# 48-pin.net
KiCad netlist of a schematic drawn in EAGLE
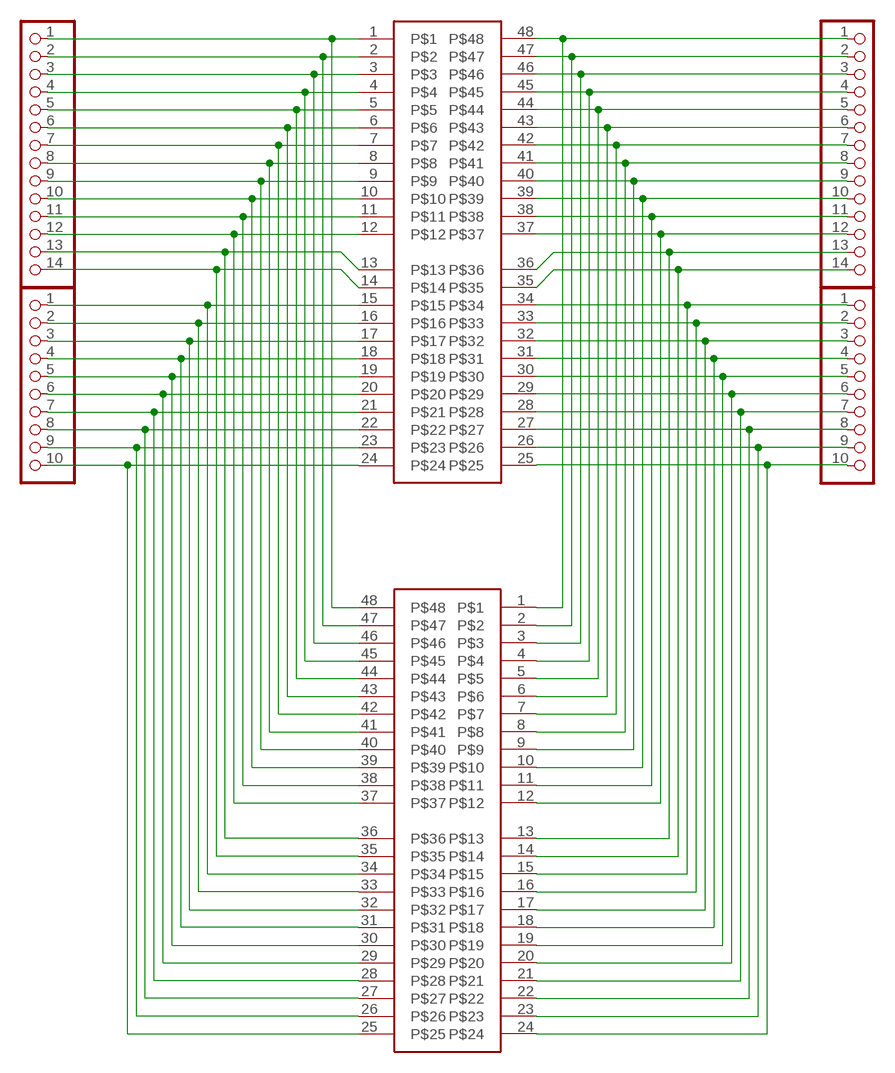
[diagram p0: schematic, sheet 1]

(export (version "E")
  (design (tool "Eeschema 10.0.6"))
  (components
    (comp (ref "JP1")
      (value "PADS-14")
      (footprint "eagle-import:PADS-14")
      (libsource (lib "eagle-import") (part "PADS-14"))
    )
    (comp (ref "JP2")
      (value "PADS-14")
      (footprint "eagle-import:PADS-14")
      (libsource (lib "eagle-import") (part "PADS-14"))
    )
    (comp (ref "JP3")
      (value "PADS-10")
      (footprint "eagle-import:PADS-10")
      (libsource (lib "eagle-import") (part "PADS-10"))
    )
    (comp (ref "JP4")
      (value "PADS-10")
      (footprint "eagle-import:PADS-10")
      (libsource (lib "eagle-import") (part "PADS-10"))
    )
    (comp (ref "U$1")
      (value "BREAKOUTS_48-PINTQFP")
      (footprint "eagle-import:BREAKOUTS_TQFP48")
      (libsource (lib "eagle-import") (part "BREAKOUTS_48-PINTQFP"))
    )
    (comp (ref "U$2")
      (value "BREAKOUTS_48-PINQFN")
      (footprint "eagle-import:BREAKOUTS_QFN48")
      (libsource (lib "eagle-import") (part "BREAKOUTS_48-PINQFN"))
    )
  )
  (nets
    (net (code "1") (name "Net-(U$1-P$1)") (class "Default")
      (node (ref "JP1") (pin "1") (pinfunction "1_1") (pintype "passive"))
      (node (ref "U$1") (pin "1") (pinfunction "P$1_1") (pintype "bidirectional"))
      (node (ref "U$2") (pin "48") (pinfunction "P$48_48") (pintype "bidirectional"))
    )
    (net (code "2") (name "Net-(U$1-P$2)") (class "Default")
      (node (ref "JP1") (pin "2") (pinfunction "2_2") (pintype "passive"))
      (node (ref "U$1") (pin "2") (pinfunction "P$2_2") (pintype "bidirectional"))
      (node (ref "U$2") (pin "47") (pinfunction "P$47_47") (pintype "bidirectional"))
    )
    (net (code "3") (name "Net-(U$1-P$3)") (class "Default")
      (node (ref "JP1") (pin "3") (pinfunction "3_3") (pintype "passive"))
      (node (ref "U$1") (pin "3") (pinfunction "P$3_3") (pintype "bidirectional"))
      (node (ref "U$2") (pin "46") (pinfunction "P$46_46") (pintype "bidirectional"))
    )
    (net (code "4") (name "Net-(U$1-P$4)") (class "Default")
      (node (ref "JP1") (pin "4") (pinfunction "4_4") (pintype "passive"))
      (node (ref "U$1") (pin "4") (pinfunction "P$4_4") (pintype "bidirectional"))
      (node (ref "U$2") (pin "45") (pinfunction "P$45_45") (pintype "bidirectional"))
    )
    (net (code "5") (name "Net-(U$1-P$5)") (class "Default")
      (node (ref "JP1") (pin "5") (pinfunction "5_5") (pintype "passive"))
      (node (ref "U$1") (pin "5") (pinfunction "P$5_5") (pintype "bidirectional"))
      (node (ref "U$2") (pin "44") (pinfunction "P$44_44") (pintype "bidirectional"))
    )
    (net (code "6") (name "Net-(U$1-P$6)") (class "Default")
      (node (ref "JP1") (pin "6") (pinfunction "6_6") (pintype "passive"))
      (node (ref "U$1") (pin "6") (pinfunction "P$6_6") (pintype "bidirectional"))
      (node (ref "U$2") (pin "43") (pinfunction "P$43_43") (pintype "bidirectional"))
    )
    (net (code "7") (name "Net-(U$1-P$7)") (class "Default")
      (node (ref "JP1") (pin "7") (pinfunction "7_7") (pintype "passive"))
      (node (ref "U$1") (pin "7") (pinfunction "P$7_7") (pintype "bidirectional"))
      (node (ref "U$2") (pin "42") (pinfunction "P$42_42") (pintype "bidirectional"))
    )
    (net (code "8") (name "Net-(U$1-P$8)") (class "Default")
      (node (ref "JP1") (pin "8") (pinfunction "8_8") (pintype "passive"))
      (node (ref "U$1") (pin "8") (pinfunction "P$8_8") (pintype "bidirectional"))
      (node (ref "U$2") (pin "41") (pinfunction "P$41_41") (pintype "bidirectional"))
    )
    (net (code "9") (name "Net-(U$1-P$9)") (class "Default")
      (node (ref "JP1") (pin "9") (pinfunction "9_9") (pintype "passive"))
      (node (ref "U$1") (pin "9") (pinfunction "P$9_9") (pintype "bidirectional"))
      (node (ref "U$2") (pin "40") (pinfunction "P$40_40") (pintype "bidirectional"))
    )
    (net (code "10") (name "Net-(U$1-P$10)") (class "Default")
      (node (ref "JP1") (pin "10") (pinfunction "10_10") (pintype "passive"))
      (node (ref "U$1") (pin "10") (pinfunction "P$10_10") (pintype "bidirectional"))
      (node (ref "U$2") (pin "39") (pinfunction "P$39_39") (pintype "bidirectional"))
    )
    (net (code "11") (name "Net-(U$1-P$11)") (class "Default")
      (node (ref "JP1") (pin "11") (pinfunction "11_11") (pintype "passive"))
      (node (ref "U$1") (pin "11") (pinfunction "P$11_11") (pintype "bidirectional"))
      (node (ref "U$2") (pin "38") (pinfunction "P$38_38") (pintype "bidirectional"))
    )
    (net (code "12") (name "Net-(U$1-P$12)") (class "Default")
      (node (ref "JP1") (pin "12") (pinfunction "12_12") (pintype "passive"))
      (node (ref "U$1") (pin "12") (pinfunction "P$12_12") (pintype "bidirectional"))
      (node (ref "U$2") (pin "37") (pinfunction "P$37_37") (pintype "bidirectional"))
    )
    (net (code "13") (name "Net-(U$1-P$13)") (class "Default")
      (node (ref "JP1") (pin "13") (pinfunction "13_13") (pintype "passive"))
      (node (ref "U$1") (pin "13") (pinfunction "P$13_13") (pintype "bidirectional"))
      (node (ref "U$2") (pin "36") (pinfunction "P$36_36") (pintype "bidirectional"))
    )
    (net (code "14") (name "Net-(U$1-P$14)") (class "Default")
      (node (ref "JP1") (pin "14") (pinfunction "14_14") (pintype "passive"))
      (node (ref "U$1") (pin "14") (pinfunction "P$14_14") (pintype "bidirectional"))
      (node (ref "U$2") (pin "35") (pinfunction "P$35_35") (pintype "bidirectional"))
    )
    (net (code "15") (name "Net-(U$1-P$15)") (class "Default")
      (node (ref "JP3") (pin "1") (pinfunction "1_1") (pintype "passive"))
      (node (ref "U$1") (pin "15") (pinfunction "P$15_15") (pintype "bidirectional"))
      (node (ref "U$2") (pin "34") (pinfunction "P$34_34") (pintype "bidirectional"))
    )
    (net (code "16") (name "Net-(U$1-P$16)") (class "Default")
      (node (ref "JP3") (pin "2") (pinfunction "2_2") (pintype "passive"))
      (node (ref "U$1") (pin "16") (pinfunction "P$16_16") (pintype "bidirectional"))
      (node (ref "U$2") (pin "33") (pinfunction "P$33_33") (pintype "bidirectional"))
    )
    (net (code "17") (name "Net-(U$1-P$17)") (class "Default")
      (node (ref "JP3") (pin "3") (pinfunction "3_3") (pintype "passive"))
      (node (ref "U$1") (pin "17") (pinfunction "P$17_17") (pintype "bidirectional"))
      (node (ref "U$2") (pin "32") (pinfunction "P$32_32") (pintype "bidirectional"))
    )
    (net (code "18") (name "Net-(U$1-P$18)") (class "Default")
      (node (ref "JP3") (pin "4") (pinfunction "4_4") (pintype "passive"))
      (node (ref "U$1") (pin "18") (pinfunction "P$18_18") (pintype "bidirectional"))
      (node (ref "U$2") (pin "31") (pinfunction "P$31_31") (pintype "bidirectional"))
    )
    (net (code "19") (name "Net-(U$1-P$19)") (class "Default")
      (node (ref "JP3") (pin "5") (pinfunction "5_5") (pintype "passive"))
      (node (ref "U$1") (pin "19") (pinfunction "P$19_19") (pintype "bidirectional"))
      (node (ref "U$2") (pin "30") (pinfunction "P$30_30") (pintype "bidirectional"))
    )
    (net (code "20") (name "Net-(U$1-P$20)") (class "Default")
      (node (ref "JP3") (pin "6") (pinfunction "6_6") (pintype "passive"))
      (node (ref "U$1") (pin "20") (pinfunction "P$20_20") (pintype "bidirectional"))
      (node (ref "U$2") (pin "29") (pinfunction "P$29_29") (pintype "bidirectional"))
    )
    (net (code "21") (name "Net-(U$1-P$21)") (class "Default")
      (node (ref "JP3") (pin "7") (pinfunction "7_7") (pintype "passive"))
      (node (ref "U$1") (pin "21") (pinfunction "P$21_21") (pintype "bidirectional"))
      (node (ref "U$2") (pin "28") (pinfunction "P$28_28") (pintype "bidirectional"))
    )
    (net (code "22") (name "Net-(U$1-P$22)") (class "Default")
      (node (ref "JP3") (pin "8") (pinfunction "8_8") (pintype "passive"))
      (node (ref "U$1") (pin "22") (pinfunction "P$22_22") (pintype "bidirectional"))
      (node (ref "U$2") (pin "27") (pinfunction "P$27_27") (pintype "bidirectional"))
    )
    (net (code "23") (name "Net-(U$1-P$23)") (class "Default")
      (node (ref "JP3") (pin "9") (pinfunction "9_9") (pintype "passive"))
      (node (ref "U$1") (pin "23") (pinfunction "P$23_23") (pintype "bidirectional"))
      (node (ref "U$2") (pin "26") (pinfunction "P$26_26") (pintype "bidirectional"))
    )
    (net (code "24") (name "Net-(U$1-P$24)") (class "Default")
      (node (ref "JP3") (pin "10") (pinfunction "10_10") (pintype "passive"))
      (node (ref "U$1") (pin "24") (pinfunction "P$24_24") (pintype "bidirectional"))
      (node (ref "U$2") (pin "25") (pinfunction "P$25_25") (pintype "bidirectional"))
    )
    (net (code "25") (name "Net-(U$1-P$25)") (class "Default")
      (node (ref "JP4") (pin "10") (pinfunction "10_10") (pintype "passive"))
      (node (ref "U$1") (pin "25") (pinfunction "P$25_25") (pintype "bidirectional"))
      (node (ref "U$2") (pin "24") (pinfunction "P$24_24") (pintype "bidirectional"))
    )
    (net (code "26") (name "Net-(U$1-P$26)") (class "Default")
      (node (ref "JP4") (pin "9") (pinfunction "9_9") (pintype "passive"))
      (node (ref "U$1") (pin "26") (pinfunction "P$26_26") (pintype "bidirectional"))
      (node (ref "U$2") (pin "23") (pinfunction "P$23_23") (pintype "bidirectional"))
    )
    (net (code "27") (name "Net-(U$1-P$27)") (class "Default")
      (node (ref "JP4") (pin "8") (pinfunction "8_8") (pintype "passive"))
      (node (ref "U$1") (pin "27") (pinfunction "P$27_27") (pintype "bidirectional"))
      (node (ref "U$2") (pin "22") (pinfunction "P$22_22") (pintype "bidirectional"))
    )
    (net (code "28") (name "Net-(U$1-P$28)") (class "Default")
      (node (ref "JP4") (pin "7") (pinfunction "7_7") (pintype "passive"))
      (node (ref "U$1") (pin "28") (pinfunction "P$28_28") (pintype "bidirectional"))
      (node (ref "U$2") (pin "21") (pinfunction "P$21_21") (pintype "bidirectional"))
    )
    (net (code "29") (name "Net-(U$1-P$29)") (class "Default")
      (node (ref "JP4") (pin "6") (pinfunction "6_6") (pintype "passive"))
      (node (ref "U$1") (pin "29") (pinfunction "P$29_29") (pintype "bidirectional"))
      (node (ref "U$2") (pin "20") (pinfunction "P$20_20") (pintype "bidirectional"))
    )
    (net (code "30") (name "Net-(U$1-P$30)") (class "Default")
      (node (ref "JP4") (pin "5") (pinfunction "5_5") (pintype "passive"))
      (node (ref "U$1") (pin "30") (pinfunction "P$30_30") (pintype "bidirectional"))
      (node (ref "U$2") (pin "19") (pinfunction "P$19_19") (pintype "bidirectional"))
    )
    (net (code "31") (name "Net-(U$1-P$31)") (class "Default")
      (node (ref "JP4") (pin "4") (pinfunction "4_4") (pintype "passive"))
      (node (ref "U$1") (pin "31") (pinfunction "P$31_31") (pintype "bidirectional"))
      (node (ref "U$2") (pin "18") (pinfunction "P$18_18") (pintype "bidirectional"))
    )
    (net (code "32") (name "Net-(U$1-P$32)") (class "Default")
      (node (ref "JP4") (pin "3") (pinfunction "3_3") (pintype "passive"))
      (node (ref "U$1") (pin "32") (pinfunction "P$32_32") (pintype "bidirectional"))
      (node (ref "U$2") (pin "17") (pinfunction "P$17_17") (pintype "bidirectional"))
    )
    (net (code "33") (name "Net-(U$1-P$33)") (class "Default")
      (node (ref "JP4") (pin "2") (pinfunction "2_2") (pintype "passive"))
      (node (ref "U$1") (pin "33") (pinfunction "P$33_33") (pintype "bidirectional"))
      (node (ref "U$2") (pin "16") (pinfunction "P$16_16") (pintype "bidirectional"))
    )
    (net (code "34") (name "Net-(U$1-P$34)") (class "Default")
      (node (ref "JP4") (pin "1") (pinfunction "1_1") (pintype "passive"))
      (node (ref "U$1") (pin "34") (pinfunction "P$34_34") (pintype "bidirectional"))
      (node (ref "U$2") (pin "15") (pinfunction "P$15_15") (pintype "bidirectional"))
    )
    (net (code "35") (name "Net-(U$1-P$35)") (class "Default")
      (node (ref "JP2") (pin "14") (pinfunction "14_14") (pintype "passive"))
      (node (ref "U$1") (pin "35") (pinfunction "P$35_35") (pintype "bidirectional"))
      (node (ref "U$2") (pin "14") (pinfunction "P$14_14") (pintype "bidirectional"))
    )
    (net (code "36") (name "Net-(U$1-P$36)") (class "Default")
      (node (ref "JP2") (pin "13") (pinfunction "13_13") (pintype "passive"))
      (node (ref "U$1") (pin "36") (pinfunction "P$36_36") (pintype "bidirectional"))
      (node (ref "U$2") (pin "13") (pinfunction "P$13_13") (pintype "bidirectional"))
    )
    (net (code "37") (name "Net-(U$1-P$37)") (class "Default")
      (node (ref "JP2") (pin "12") (pinfunction "12_12") (pintype "passive"))
      (node (ref "U$1") (pin "37") (pinfunction "P$37_37") (pintype "bidirectional"))
      (node (ref "U$2") (pin "12") (pinfunction "P$12_12") (pintype "bidirectional"))
    )
    (net (code "38") (name "Net-(U$1-P$38)") (class "Default")
      (node (ref "JP2") (pin "11") (pinfunction "11_11") (pintype "passive"))
      (node (ref "U$1") (pin "38") (pinfunction "P$38_38") (pintype "bidirectional"))
      (node (ref "U$2") (pin "11") (pinfunction "P$11_11") (pintype "bidirectional"))
    )
    (net (code "39") (name "Net-(U$1-P$39)") (class "Default")
      (node (ref "JP2") (pin "10") (pinfunction "10_10") (pintype "passive"))
      (node (ref "U$1") (pin "39") (pinfunction "P$39_39") (pintype "bidirectional"))
      (node (ref "U$2") (pin "10") (pinfunction "P$10_10") (pintype "bidirectional"))
    )
    (net (code "40") (name "Net-(U$1-P$40)") (class "Default")
      (node (ref "JP2") (pin "9") (pinfunction "9_9") (pintype "passive"))
      (node (ref "U$1") (pin "40") (pinfunction "P$40_40") (pintype "bidirectional"))
      (node (ref "U$2") (pin "9") (pinfunction "P$9_9") (pintype "bidirectional"))
    )
    (net (code "41") (name "Net-(U$1-P$41)") (class "Default")
      (node (ref "JP2") (pin "8") (pinfunction "8_8") (pintype "passive"))
      (node (ref "U$1") (pin "41") (pinfunction "P$41_41") (pintype "bidirectional"))
      (node (ref "U$2") (pin "8") (pinfunction "P$8_8") (pintype "bidirectional"))
    )
    (net (code "42") (name "Net-(U$1-P$42)") (class "Default")
      (node (ref "JP2") (pin "7") (pinfunction "7_7") (pintype "passive"))
      (node (ref "U$1") (pin "42") (pinfunction "P$42_42") (pintype "bidirectional"))
      (node (ref "U$2") (pin "7") (pinfunction "P$7_7") (pintype "bidirectional"))
    )
    (net (code "43") (name "Net-(U$1-P$43)") (class "Default")
      (node (ref "JP2") (pin "6") (pinfunction "6_6") (pintype "passive"))
      (node (ref "U$1") (pin "43") (pinfunction "P$43_43") (pintype "bidirectional"))
      (node (ref "U$2") (pin "6") (pinfunction "P$6_6") (pintype "bidirectional"))
    )
    (net (code "44") (name "Net-(U$1-P$44)") (class "Default")
      (node (ref "JP2") (pin "5") (pinfunction "5_5") (pintype "passive"))
      (node (ref "U$1") (pin "44") (pinfunction "P$44_44") (pintype "bidirectional"))
      (node (ref "U$2") (pin "5") (pinfunction "P$5_5") (pintype "bidirectional"))
    )
    (net (code "45") (name "Net-(U$1-P$45)") (class "Default")
      (node (ref "JP2") (pin "4") (pinfunction "4_4") (pintype "passive"))
      (node (ref "U$1") (pin "45") (pinfunction "P$45_45") (pintype "bidirectional"))
      (node (ref "U$2") (pin "4") (pinfunction "P$4_4") (pintype "bidirectional"))
    )
    (net (code "46") (name "Net-(U$1-P$46)") (class "Default")
      (node (ref "JP2") (pin "3") (pinfunction "3_3") (pintype "passive"))
      (node (ref "U$1") (pin "46") (pinfunction "P$46_46") (pintype "bidirectional"))
      (node (ref "U$2") (pin "3") (pinfunction "P$3_3") (pintype "bidirectional"))
    )
    (net (code "47") (name "Net-(U$1-P$47)") (class "Default")
      (node (ref "JP2") (pin "2") (pinfunction "2_2") (pintype "passive"))
      (node (ref "U$1") (pin "47") (pinfunction "P$47_47") (pintype "bidirectional"))
      (node (ref "U$2") (pin "2") (pinfunction "P$2_2") (pintype "bidirectional"))
    )
    (net (code "48") (name "Net-(U$1-P$48)") (class "Default")
      (node (ref "JP2") (pin "1") (pinfunction "1_1") (pintype "passive"))
      (node (ref "U$1") (pin "48") (pinfunction "P$48_48") (pintype "bidirectional"))
      (node (ref "U$2") (pin "1") (pinfunction "P$1_1") (pintype "bidirectional"))
    )
  )
)
